# P1001-001-013-320_-_Bus_Debugger.net
KiCad netlist of a schematic drawn in EAGLE
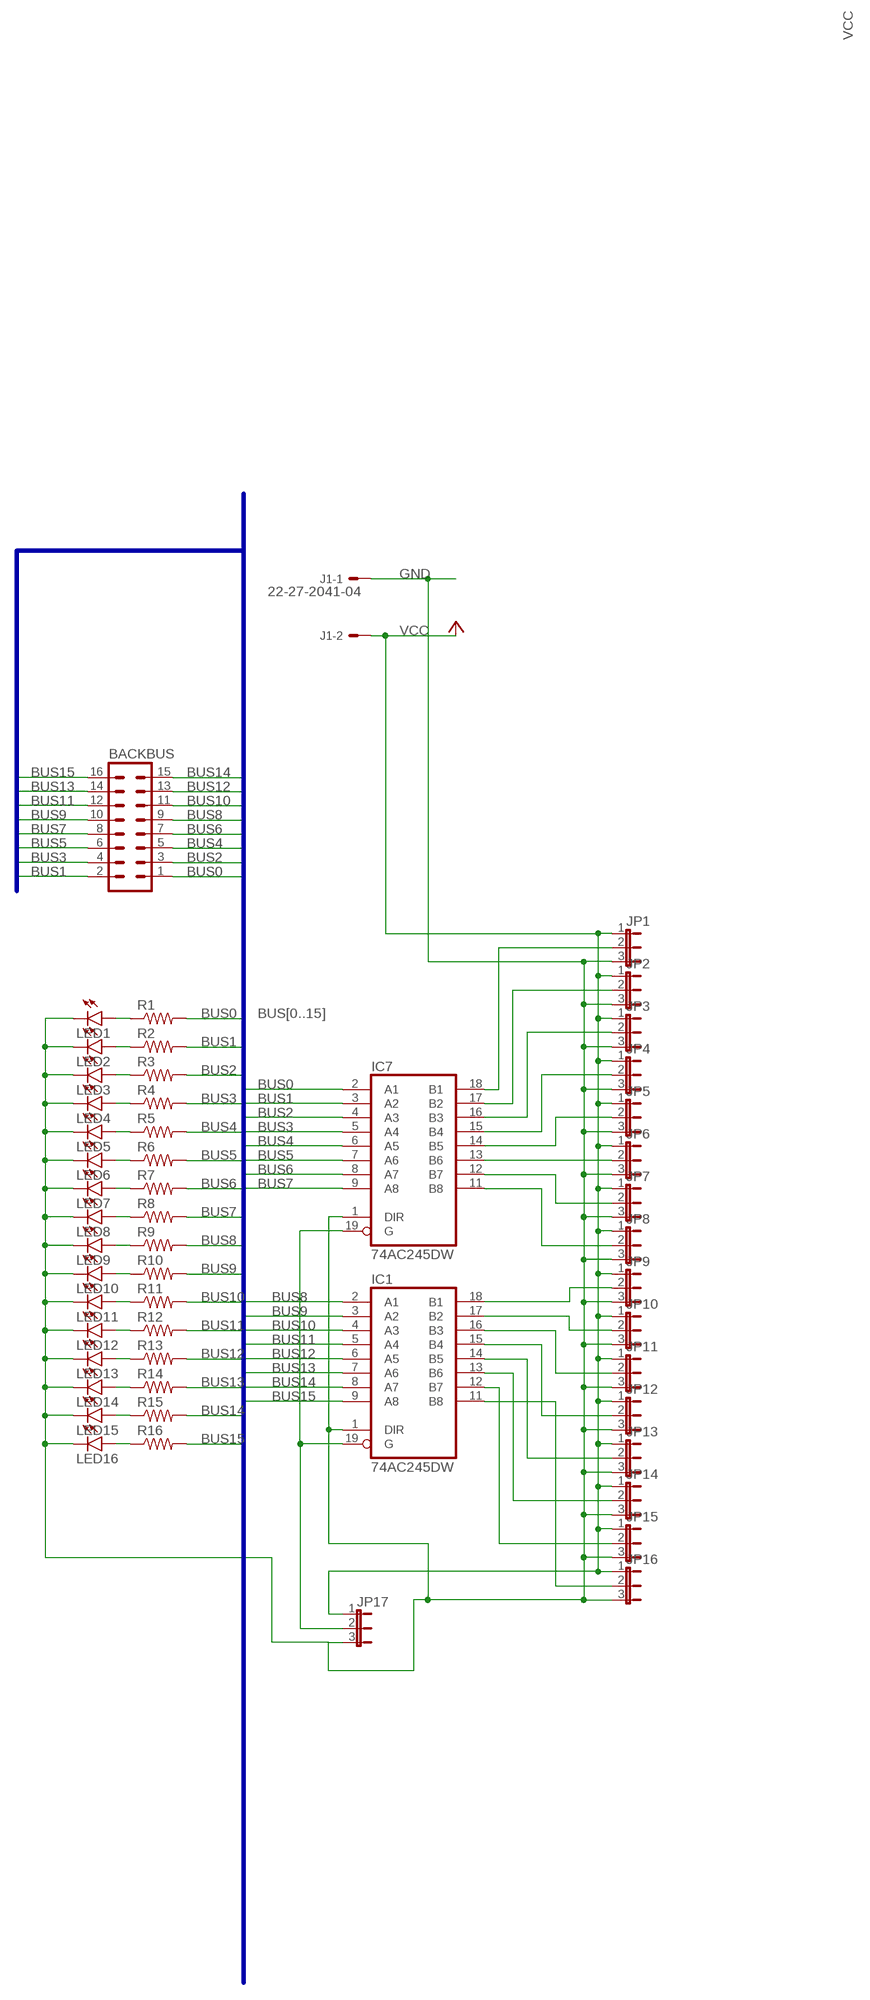
[diagram p0: schematic, sheet 1]

(export (version "E")
  (design (tool "Eeschema 10.0.6"))
  (components
    (comp (ref "BACKBUS")
      (value "ML16")
      (footprint "eagle-import:ML16")
      (libsource (lib "eagle-import") (part "ML16"))
    )
    (comp (ref "IC1")
      (value "74AC245DW")
      (footprint "eagle-import:SO20W")
      (libsource (lib "eagle-import") (part "74245DWAC"))
    )
    (comp (ref "IC7")
      (value "74AC245DW")
      (footprint "eagle-import:SO20W")
      (libsource (lib "eagle-import") (part "74245DWAC"))
    )
    (comp (ref "J1")
      (value "22-27-2041-04")
      (footprint "eagle-import:6410-04")
      (fields (field (name "MF") "MOLEX"))
      (libsource (lib "eagle-import") (part "22-?-0427-2041"))
    )
    (comp (ref "JP1")
      (value "JP2E")
      (footprint "eagle-import:JP2")
      (libsource (lib "eagle-import") (part "JP2E"))
    )
    (comp (ref "JP2")
      (value "JP2E")
      (footprint "eagle-import:JP2")
      (libsource (lib "eagle-import") (part "JP2E"))
    )
    (comp (ref "JP3")
      (value "JP2E")
      (footprint "eagle-import:JP2")
      (libsource (lib "eagle-import") (part "JP2E"))
    )
    (comp (ref "JP4")
      (value "JP2E")
      (footprint "eagle-import:JP2")
      (libsource (lib "eagle-import") (part "JP2E"))
    )
    (comp (ref "JP5")
      (value "JP2E")
      (footprint "eagle-import:JP2")
      (libsource (lib "eagle-import") (part "JP2E"))
    )
    (comp (ref "JP6")
      (value "JP2E")
      (footprint "eagle-import:JP2")
      (libsource (lib "eagle-import") (part "JP2E"))
    )
    (comp (ref "JP7")
      (value "JP2E")
      (footprint "eagle-import:JP2")
      (libsource (lib "eagle-import") (part "JP2E"))
    )
    (comp (ref "JP8")
      (value "JP2E")
      (footprint "eagle-import:JP2")
      (libsource (lib "eagle-import") (part "JP2E"))
    )
    (comp (ref "JP9")
      (value "JP2E")
      (footprint "eagle-import:JP2")
      (libsource (lib "eagle-import") (part "JP2E"))
    )
    (comp (ref "JP10")
      (value "JP2E")
      (footprint "eagle-import:JP2")
      (libsource (lib "eagle-import") (part "JP2E"))
    )
    (comp (ref "JP11")
      (value "JP2E")
      (footprint "eagle-import:JP2")
      (libsource (lib "eagle-import") (part "JP2E"))
    )
    (comp (ref "JP12")
      (value "JP2E")
      (footprint "eagle-import:JP2")
      (libsource (lib "eagle-import") (part "JP2E"))
    )
    (comp (ref "JP13")
      (value "JP2E")
      (footprint "eagle-import:JP2")
      (libsource (lib "eagle-import") (part "JP2E"))
    )
    (comp (ref "JP14")
      (value "JP2E")
      (footprint "eagle-import:JP2")
      (libsource (lib "eagle-import") (part "JP2E"))
    )
    (comp (ref "JP15")
      (value "JP2E")
      (footprint "eagle-import:JP2")
      (libsource (lib "eagle-import") (part "JP2E"))
    )
    (comp (ref "JP16")
      (value "JP2E")
      (footprint "eagle-import:JP2")
      (libsource (lib "eagle-import") (part "JP2E"))
    )
    (comp (ref "JP17")
      (value "JP2E")
      (footprint "eagle-import:JP2")
      (libsource (lib "eagle-import") (part "JP2E"))
    )
    (comp (ref "LED1")
      (value "LED5MM")
      (footprint "eagle-import:LED5MM")
      (libsource (lib "eagle-import") (part "LED5MM"))
    )
    (comp (ref "LED2")
      (value "LED5MM")
      (footprint "eagle-import:LED5MM")
      (libsource (lib "eagle-import") (part "LED5MM"))
    )
    (comp (ref "LED3")
      (value "LED5MM")
      (footprint "eagle-import:LED5MM")
      (libsource (lib "eagle-import") (part "LED5MM"))
    )
    (comp (ref "LED4")
      (value "LED5MM")
      (footprint "eagle-import:LED5MM")
      (libsource (lib "eagle-import") (part "LED5MM"))
    )
    (comp (ref "LED5")
      (value "LED5MM")
      (footprint "eagle-import:LED5MM")
      (libsource (lib "eagle-import") (part "LED5MM"))
    )
    (comp (ref "LED6")
      (value "LED5MM")
      (footprint "eagle-import:LED5MM")
      (libsource (lib "eagle-import") (part "LED5MM"))
    )
    (comp (ref "LED7")
      (value "LED5MM")
      (footprint "eagle-import:LED5MM")
      (libsource (lib "eagle-import") (part "LED5MM"))
    )
    (comp (ref "LED8")
      (value "LED5MM")
      (footprint "eagle-import:LED5MM")
      (libsource (lib "eagle-import") (part "LED5MM"))
    )
    (comp (ref "LED9")
      (value "LED5MM")
      (footprint "eagle-import:LED5MM")
      (libsource (lib "eagle-import") (part "LED5MM"))
    )
    (comp (ref "LED10")
      (value "LED5MM")
      (footprint "eagle-import:LED5MM")
      (libsource (lib "eagle-import") (part "LED5MM"))
    )
    (comp (ref "LED11")
      (value "LED5MM")
      (footprint "eagle-import:LED5MM")
      (libsource (lib "eagle-import") (part "LED5MM"))
    )
    (comp (ref "LED12")
      (value "LED5MM")
      (footprint "eagle-import:LED5MM")
      (libsource (lib "eagle-import") (part "LED5MM"))
    )
    (comp (ref "LED13")
      (value "LED5MM")
      (footprint "eagle-import:LED5MM")
      (libsource (lib "eagle-import") (part "LED5MM"))
    )
    (comp (ref "LED14")
      (value "LED5MM")
      (footprint "eagle-import:LED5MM")
      (libsource (lib "eagle-import") (part "LED5MM"))
    )
    (comp (ref "LED15")
      (value "LED5MM")
      (footprint "eagle-import:LED5MM")
      (libsource (lib "eagle-import") (part "LED5MM"))
    )
    (comp (ref "LED16")
      (value "LED5MM")
      (footprint "eagle-import:LED5MM")
      (libsource (lib "eagle-import") (part "LED5MM"))
    )
    (comp (ref "R1")
      (value "R-US_0204/2V")
      (footprint "eagle-import:0204V")
      (libsource (lib "eagle-import") (part "R-US_0204/2V"))
    )
    (comp (ref "R2")
      (value "R-US_0204/2V")
      (footprint "eagle-import:0204V")
      (libsource (lib "eagle-import") (part "R-US_0204/2V"))
    )
    (comp (ref "R3")
      (value "R-US_0204/2V")
      (footprint "eagle-import:0204V")
      (libsource (lib "eagle-import") (part "R-US_0204/2V"))
    )
    (comp (ref "R4")
      (value "R-US_0204/2V")
      (footprint "eagle-import:0204V")
      (libsource (lib "eagle-import") (part "R-US_0204/2V"))
    )
    (comp (ref "R5")
      (value "R-US_0204/2V")
      (footprint "eagle-import:0204V")
      (libsource (lib "eagle-import") (part "R-US_0204/2V"))
    )
    (comp (ref "R6")
      (value "R-US_0204/2V")
      (footprint "eagle-import:0204V")
      (libsource (lib "eagle-import") (part "R-US_0204/2V"))
    )
    (comp (ref "R7")
      (value "R-US_0204/2V")
      (footprint "eagle-import:0204V")
      (libsource (lib "eagle-import") (part "R-US_0204/2V"))
    )
    (comp (ref "R8")
      (value "R-US_0204/2V")
      (footprint "eagle-import:0204V")
      (libsource (lib "eagle-import") (part "R-US_0204/2V"))
    )
    (comp (ref "R9")
      (value "R-US_0204/2V")
      (footprint "eagle-import:0204V")
      (libsource (lib "eagle-import") (part "R-US_0204/2V"))
    )
    (comp (ref "R10")
      (value "R-US_0204/2V")
      (footprint "eagle-import:0204V")
      (libsource (lib "eagle-import") (part "R-US_0204/2V"))
    )
    (comp (ref "R11")
      (value "R-US_0204/2V")
      (footprint "eagle-import:0204V")
      (libsource (lib "eagle-import") (part "R-US_0204/2V"))
    )
    (comp (ref "R12")
      (value "R-US_0204/2V")
      (footprint "eagle-import:0204V")
      (libsource (lib "eagle-import") (part "R-US_0204/2V"))
    )
    (comp (ref "R13")
      (value "R-US_0204/2V")
      (footprint "eagle-import:0204V")
      (libsource (lib "eagle-import") (part "R-US_0204/2V"))
    )
    (comp (ref "R14")
      (value "R-US_0204/2V")
      (footprint "eagle-import:0204V")
      (libsource (lib "eagle-import") (part "R-US_0204/2V"))
    )
    (comp (ref "R15")
      (value "R-US_0204/2V")
      (footprint "eagle-import:0204V")
      (libsource (lib "eagle-import") (part "R-US_0204/2V"))
    )
    (comp (ref "R16")
      (value "R-US_0204/2V")
      (footprint "eagle-import:0204V")
      (libsource (lib "eagle-import") (part "R-US_0204/2V"))
    )
  )
  (nets
    (net (code "1") (name "/BUS0") (class "Default")
      (node (ref "BACKBUS") (pin "1") (pinfunction "1_1") (pintype "passive"))
      (node (ref "IC7") (pin "2") (pinfunction "A1_2") (pintype "bidirectional"))
      (node (ref "R1") (pin "2") (pinfunction "2_2") (pintype "passive"))
    )
    (net (code "2") (name "/BUS1") (class "Default")
      (node (ref "BACKBUS") (pin "2") (pinfunction "2_2") (pintype "passive"))
      (node (ref "IC7") (pin "3") (pinfunction "A2_3") (pintype "bidirectional"))
      (node (ref "R2") (pin "2") (pinfunction "2_2") (pintype "passive"))
    )
    (net (code "3") (name "/BUS2") (class "Default")
      (node (ref "BACKBUS") (pin "3") (pinfunction "3_3") (pintype "passive"))
      (node (ref "IC7") (pin "4") (pinfunction "A3_4") (pintype "bidirectional"))
      (node (ref "R3") (pin "2") (pinfunction "2_2") (pintype "passive"))
    )
    (net (code "4") (name "/BUS3") (class "Default")
      (node (ref "BACKBUS") (pin "4") (pinfunction "4_4") (pintype "passive"))
      (node (ref "IC7") (pin "5") (pinfunction "A4_5") (pintype "bidirectional"))
      (node (ref "R4") (pin "2") (pinfunction "2_2") (pintype "passive"))
    )
    (net (code "5") (name "/BUS4") (class "Default")
      (node (ref "BACKBUS") (pin "5") (pinfunction "5_5") (pintype "passive"))
      (node (ref "IC7") (pin "6") (pinfunction "A5_6") (pintype "bidirectional"))
      (node (ref "R5") (pin "2") (pinfunction "2_2") (pintype "passive"))
    )
    (net (code "6") (name "/BUS5") (class "Default")
      (node (ref "BACKBUS") (pin "6") (pinfunction "6_6") (pintype "passive"))
      (node (ref "IC7") (pin "7") (pinfunction "A6_7") (pintype "bidirectional"))
      (node (ref "R6") (pin "2") (pinfunction "2_2") (pintype "passive"))
    )
    (net (code "7") (name "/BUS6") (class "Default")
      (node (ref "BACKBUS") (pin "7") (pinfunction "7_7") (pintype "passive"))
      (node (ref "IC7") (pin "8") (pinfunction "A7_8") (pintype "bidirectional"))
      (node (ref "R7") (pin "2") (pinfunction "2_2") (pintype "passive"))
    )
    (net (code "8") (name "/BUS7") (class "Default")
      (node (ref "BACKBUS") (pin "8") (pinfunction "8_8") (pintype "passive"))
      (node (ref "IC7") (pin "9") (pinfunction "A8_9") (pintype "bidirectional"))
      (node (ref "R8") (pin "2") (pinfunction "2_2") (pintype "passive"))
    )
    (net (code "9") (name "/BUS8") (class "Default")
      (node (ref "BACKBUS") (pin "9") (pinfunction "9_9") (pintype "passive"))
      (node (ref "IC1") (pin "2") (pinfunction "A1_2") (pintype "bidirectional"))
      (node (ref "R9") (pin "2") (pinfunction "2_2") (pintype "passive"))
    )
    (net (code "10") (name "/BUS9") (class "Default")
      (node (ref "BACKBUS") (pin "10") (pinfunction "10_10") (pintype "passive"))
      (node (ref "IC1") (pin "3") (pinfunction "A2_3") (pintype "bidirectional"))
      (node (ref "R10") (pin "2") (pinfunction "2_2") (pintype "passive"))
    )
    (net (code "11") (name "/BUS10") (class "Default")
      (node (ref "BACKBUS") (pin "11") (pinfunction "11_11") (pintype "passive"))
      (node (ref "IC1") (pin "4") (pinfunction "A3_4") (pintype "bidirectional"))
      (node (ref "R11") (pin "2") (pinfunction "2_2") (pintype "passive"))
    )
    (net (code "12") (name "/BUS11") (class "Default")
      (node (ref "BACKBUS") (pin "12") (pinfunction "12_12") (pintype "passive"))
      (node (ref "IC1") (pin "5") (pinfunction "A4_5") (pintype "bidirectional"))
      (node (ref "R12") (pin "2") (pinfunction "2_2") (pintype "passive"))
    )
    (net (code "13") (name "/BUS12") (class "Default")
      (node (ref "BACKBUS") (pin "13") (pinfunction "13_13") (pintype "passive"))
      (node (ref "IC1") (pin "6") (pinfunction "A5_6") (pintype "bidirectional"))
      (node (ref "R13") (pin "2") (pinfunction "2_2") (pintype "passive"))
    )
    (net (code "14") (name "/BUS13") (class "Default")
      (node (ref "BACKBUS") (pin "14") (pinfunction "14_14") (pintype "passive"))
      (node (ref "IC1") (pin "7") (pinfunction "A6_7") (pintype "bidirectional"))
      (node (ref "R14") (pin "2") (pinfunction "2_2") (pintype "passive"))
    )
    (net (code "15") (name "/BUS14") (class "Default")
      (node (ref "BACKBUS") (pin "15") (pinfunction "15_15") (pintype "passive"))
      (node (ref "IC1") (pin "8") (pinfunction "A7_8") (pintype "bidirectional"))
      (node (ref "R15") (pin "2") (pinfunction "2_2") (pintype "passive"))
    )
    (net (code "16") (name "/BUS15") (class "Default")
      (node (ref "BACKBUS") (pin "16") (pinfunction "16_16") (pintype "passive"))
      (node (ref "IC1") (pin "9") (pinfunction "A8_9") (pintype "bidirectional"))
      (node (ref "R16") (pin "2") (pinfunction "2_2") (pintype "passive"))
    )
    (net (code "18") (name "/GND") (class "Default")
      (node (ref "IC1") (pin "1") (pinfunction "DIR_1") (pintype "input"))
      (node (ref "IC7") (pin "1") (pinfunction "DIR_1") (pintype "input"))
      (node (ref "J1") (pin "1") (pinfunction "S_1") (pintype "passive"))
      (node (ref "JP1") (pin "3") (pinfunction "3_3") (pintype "passive"))
      (node (ref "JP10") (pin "3") (pinfunction "3_3") (pintype "passive"))
      (node (ref "JP11") (pin "3") (pinfunction "3_3") (pintype "passive"))
      (node (ref "JP12") (pin "3") (pinfunction "3_3") (pintype "passive"))
      (node (ref "JP13") (pin "3") (pinfunction "3_3") (pintype "passive"))
      (node (ref "JP14") (pin "3") (pinfunction "3_3") (pintype "passive"))
      (node (ref "JP15") (pin "3") (pinfunction "3_3") (pintype "passive"))
      (node (ref "JP16") (pin "3") (pinfunction "3_3") (pintype "passive"))
      (node (ref "JP17") (pin "3") (pinfunction "3_3") (pintype "passive"))
      (node (ref "JP2") (pin "3") (pinfunction "3_3") (pintype "passive"))
      (node (ref "JP3") (pin "3") (pinfunction "3_3") (pintype "passive"))
      (node (ref "JP4") (pin "3") (pinfunction "3_3") (pintype "passive"))
      (node (ref "JP5") (pin "3") (pinfunction "3_3") (pintype "passive"))
      (node (ref "JP6") (pin "3") (pinfunction "3_3") (pintype "passive"))
      (node (ref "JP7") (pin "3") (pinfunction "3_3") (pintype "passive"))
      (node (ref "JP8") (pin "3") (pinfunction "3_3") (pintype "passive"))
      (node (ref "JP9") (pin "3") (pinfunction "3_3") (pintype "passive"))
      (node (ref "LED1") (pin "K") (pinfunction "C_K") (pintype "passive"))
      (node (ref "LED10") (pin "K") (pinfunction "C_K") (pintype "passive"))
      (node (ref "LED11") (pin "K") (pinfunction "C_K") (pintype "passive"))
      (node (ref "LED12") (pin "K") (pinfunction "C_K") (pintype "passive"))
      (node (ref "LED13") (pin "K") (pinfunction "C_K") (pintype "passive"))
      (node (ref "LED14") (pin "K") (pinfunction "C_K") (pintype "passive"))
      (node (ref "LED15") (pin "K") (pinfunction "C_K") (pintype "passive"))
      (node (ref "LED16") (pin "K") (pinfunction "C_K") (pintype "passive"))
      (node (ref "LED2") (pin "K") (pinfunction "C_K") (pintype "passive"))
      (node (ref "LED3") (pin "K") (pinfunction "C_K") (pintype "passive"))
      (node (ref "LED4") (pin "K") (pinfunction "C_K") (pintype "passive"))
      (node (ref "LED5") (pin "K") (pinfunction "C_K") (pintype "passive"))
      (node (ref "LED6") (pin "K") (pinfunction "C_K") (pintype "passive"))
      (node (ref "LED7") (pin "K") (pinfunction "C_K") (pintype "passive"))
      (node (ref "LED8") (pin "K") (pinfunction "C_K") (pintype "passive"))
      (node (ref "LED9") (pin "K") (pinfunction "C_K") (pintype "passive"))
    )
    (net (code "19") (name "Net-(IC1A-B1)") (class "Default")
      (node (ref "IC1") (pin "18") (pinfunction "B1_18") (pintype "bidirectional"))
      (node (ref "JP9") (pin "2") (pinfunction "2_2") (pintype "passive"))
    )
    (net (code "20") (name "Net-(IC1A-B2)") (class "Default")
      (node (ref "IC1") (pin "17") (pinfunction "B2_17") (pintype "bidirectional"))
      (node (ref "JP10") (pin "2") (pinfunction "2_2") (pintype "passive"))
    )
    (net (code "21") (name "Net-(IC1A-B3)") (class "Default")
      (node (ref "IC1") (pin "16") (pinfunction "B3_16") (pintype "bidirectional"))
      (node (ref "JP11") (pin "2") (pinfunction "2_2") (pintype "passive"))
    )
    (net (code "22") (name "Net-(IC1A-B4)") (class "Default")
      (node (ref "IC1") (pin "15") (pinfunction "B4_15") (pintype "bidirectional"))
      (node (ref "JP12") (pin "2") (pinfunction "2_2") (pintype "passive"))
    )
    (net (code "23") (name "Net-(IC1A-B5)") (class "Default")
      (node (ref "IC1") (pin "14") (pinfunction "B5_14") (pintype "bidirectional"))
      (node (ref "JP13") (pin "2") (pinfunction "2_2") (pintype "passive"))
    )
    (net (code "24") (name "Net-(IC1A-B6)") (class "Default")
      (node (ref "IC1") (pin "13") (pinfunction "B6_13") (pintype "bidirectional"))
      (node (ref "JP14") (pin "2") (pinfunction "2_2") (pintype "passive"))
    )
    (net (code "25") (name "Net-(IC1A-B7)") (class "Default")
      (node (ref "IC1") (pin "12") (pinfunction "B7_12") (pintype "bidirectional"))
      (node (ref "JP15") (pin "2") (pinfunction "2_2") (pintype "passive"))
    )
    (net (code "26") (name "Net-(IC1A-B8)") (class "Default")
      (node (ref "IC1") (pin "11") (pinfunction "B8_11") (pintype "bidirectional"))
      (node (ref "JP16") (pin "2") (pinfunction "2_2") (pintype "passive"))
    )
    (net (code "27") (name "Net-(IC1A-G)") (class "Default")
      (node (ref "IC1") (pin "19") (pinfunction "G_19") (pintype "input"))
      (node (ref "IC7") (pin "19") (pinfunction "G_19") (pintype "input"))
      (node (ref "JP17") (pin "2") (pinfunction "2_2") (pintype "passive"))
    )
    (net (code "28") (name "Net-(IC7A-B1)") (class "Default")
      (node (ref "IC7") (pin "18") (pinfunction "B1_18") (pintype "bidirectional"))
      (node (ref "JP1") (pin "2") (pinfunction "2_2") (pintype "passive"))
    )
    (net (code "29") (name "Net-(IC7A-B2)") (class "Default")
      (node (ref "IC7") (pin "17") (pinfunction "B2_17") (pintype "bidirectional"))
      (node (ref "JP2") (pin "2") (pinfunction "2_2") (pintype "passive"))
    )
    (net (code "30") (name "Net-(IC7A-B3)") (class "Default")
      (node (ref "IC7") (pin "16") (pinfunction "B3_16") (pintype "bidirectional"))
      (node (ref "JP3") (pin "2") (pinfunction "2_2") (pintype "passive"))
    )
    (net (code "31") (name "Net-(IC7A-B4)") (class "Default")
      (node (ref "IC7") (pin "15") (pinfunction "B4_15") (pintype "bidirectional"))
      (node (ref "JP4") (pin "2") (pinfunction "2_2") (pintype "passive"))
    )
    (net (code "32") (name "Net-(IC7A-B5)") (class "Default")
      (node (ref "IC7") (pin "14") (pinfunction "B5_14") (pintype "bidirectional"))
      (node (ref "JP5") (pin "2") (pinfunction "2_2") (pintype "passive"))
    )
    (net (code "33") (name "Net-(IC7A-B6)") (class "Default")
      (node (ref "IC7") (pin "13") (pinfunction "B6_13") (pintype "bidirectional"))
      (node (ref "JP6") (pin "2") (pinfunction "2_2") (pintype "passive"))
    )
    (net (code "34") (name "Net-(IC7A-B7)") (class "Default")
      (node (ref "IC7") (pin "12") (pinfunction "B7_12") (pintype "bidirectional"))
      (node (ref "JP7") (pin "2") (pinfunction "2_2") (pintype "passive"))
    )
    (net (code "35") (name "Net-(IC7A-B8)") (class "Default")
      (node (ref "IC7") (pin "11") (pinfunction "B8_11") (pintype "bidirectional"))
      (node (ref "JP8") (pin "2") (pinfunction "2_2") (pintype "passive"))
    )
    (net (code "36") (name "Net-(LED1-PadA)") (class "Default")
      (node (ref "LED1") (pin "A") (pinfunction "A_A") (pintype "passive"))
      (node (ref "R1") (pin "1") (pinfunction "1_1") (pintype "passive"))
    )
    (net (code "37") (name "Net-(LED2-PadA)") (class "Default")
      (node (ref "LED2") (pin "A") (pinfunction "A_A") (pintype "passive"))
      (node (ref "R2") (pin "1") (pinfunction "1_1") (pintype "passive"))
    )
    (net (code "38") (name "Net-(LED3-PadA)") (class "Default")
      (node (ref "LED3") (pin "A") (pinfunction "A_A") (pintype "passive"))
      (node (ref "R3") (pin "1") (pinfunction "1_1") (pintype "passive"))
    )
    (net (code "39") (name "Net-(LED4-PadA)") (class "Default")
      (node (ref "LED4") (pin "A") (pinfunction "A_A") (pintype "passive"))
      (node (ref "R4") (pin "1") (pinfunction "1_1") (pintype "passive"))
    )
    (net (code "40") (name "Net-(LED5-PadA)") (class "Default")
      (node (ref "LED5") (pin "A") (pinfunction "A_A") (pintype "passive"))
      (node (ref "R5") (pin "1") (pinfunction "1_1") (pintype "passive"))
    )
    (net (code "41") (name "Net-(LED6-PadA)") (class "Default")
      (node (ref "LED6") (pin "A") (pinfunction "A_A") (pintype "passive"))
      (node (ref "R6") (pin "1") (pinfunction "1_1") (pintype "passive"))
    )
    (net (code "42") (name "Net-(LED7-PadA)") (class "Default")
      (node (ref "LED7") (pin "A") (pinfunction "A_A") (pintype "passive"))
      (node (ref "R7") (pin "1") (pinfunction "1_1") (pintype "passive"))
    )
    (net (code "43") (name "Net-(LED8-PadA)") (class "Default")
      (node (ref "LED8") (pin "A") (pinfunction "A_A") (pintype "passive"))
      (node (ref "R8") (pin "1") (pinfunction "1_1") (pintype "passive"))
    )
    (net (code "44") (name "Net-(LED9-PadA)") (class "Default")
      (node (ref "LED9") (pin "A") (pinfunction "A_A") (pintype "passive"))
      (node (ref "R9") (pin "1") (pinfunction "1_1") (pintype "passive"))
    )
    (net (code "45") (name "Net-(LED10-PadA)") (class "Default")
      (node (ref "LED10") (pin "A") (pinfunction "A_A") (pintype "passive"))
      (node (ref "R10") (pin "1") (pinfunction "1_1") (pintype "passive"))
    )
    (net (code "46") (name "Net-(LED11-PadA)") (class "Default")
      (node (ref "LED11") (pin "A") (pinfunction "A_A") (pintype "passive"))
      (node (ref "R11") (pin "1") (pinfunction "1_1") (pintype "passive"))
    )
    (net (code "47") (name "Net-(LED12-PadA)") (class "Default")
      (node (ref "LED12") (pin "A") (pinfunction "A_A") (pintype "passive"))
      (node (ref "R12") (pin "1") (pinfunction "1_1") (pintype "passive"))
    )
    (net (code "48") (name "Net-(LED13-PadA)") (class "Default")
      (node (ref "LED13") (pin "A") (pinfunction "A_A") (pintype "passive"))
      (node (ref "R13") (pin "1") (pinfunction "1_1") (pintype "passive"))
    )
    (net (code "49") (name "Net-(LED14-PadA)") (class "Default")
      (node (ref "LED14") (pin "A") (pinfunction "A_A") (pintype "passive"))
      (node (ref "R14") (pin "1") (pinfunction "1_1") (pintype "passive"))
    )
    (net (code "50") (name "Net-(LED15-PadA)") (class "Default")
      (node (ref "LED15") (pin "A") (pinfunction "A_A") (pintype "passive"))
      (node (ref "R15") (pin "1") (pinfunction "1_1") (pintype "passive"))
    )
    (net (code "51") (name "Net-(LED16-PadA)") (class "Default")
      (node (ref "LED16") (pin "A") (pinfunction "A_A") (pintype "passive"))
      (node (ref "R16") (pin "1") (pinfunction "1_1") (pintype "passive"))
    )
    (net (code "52") (name "VCC") (class "Default")
      (node (ref "J1") (pin "2") (pinfunction "S_2") (pintype "passive"))
      (node (ref "JP1") (pin "1") (pinfunction "1_1") (pintype "passive"))
      (node (ref "JP10") (pin "1") (pinfunction "1_1") (pintype "passive"))
      (node (ref "JP11") (pin "1") (pinfunction "1_1") (pintype "passive"))
      (node (ref "JP12") (pin "1") (pinfunction "1_1") (pintype "passive"))
      (node (ref "JP13") (pin "1") (pinfunction "1_1") (pintype "passive"))
      (node (ref "JP14") (pin "1") (pinfunction "1_1") (pintype "passive"))
      (node (ref "JP15") (pin "1") (pinfunction "1_1") (pintype "passive"))
      (node (ref "JP16") (pin "1") (pinfunction "1_1") (pintype "passive"))
      (node (ref "JP17") (pin "1") (pinfunction "1_1") (pintype "passive"))
      (node (ref "JP2") (pin "1") (pinfunction "1_1") (pintype "passive"))
      (node (ref "JP3") (pin "1") (pinfunction "1_1") (pintype "passive"))
      (node (ref "JP4") (pin "1") (pinfunction "1_1") (pintype "passive"))
      (node (ref "JP5") (pin "1") (pinfunction "1_1") (pintype "passive"))
      (node (ref "JP6") (pin "1") (pinfunction "1_1") (pintype "passive"))
      (node (ref "JP7") (pin "1") (pinfunction "1_1") (pintype "passive"))
      (node (ref "JP8") (pin "1") (pinfunction "1_1") (pintype "passive"))
      (node (ref "JP9") (pin "1") (pinfunction "1_1") (pintype "passive"))
    )
  )
)
